# Level_Shifter.net
KiCad netlist of a schematic drawn in Altium Designer
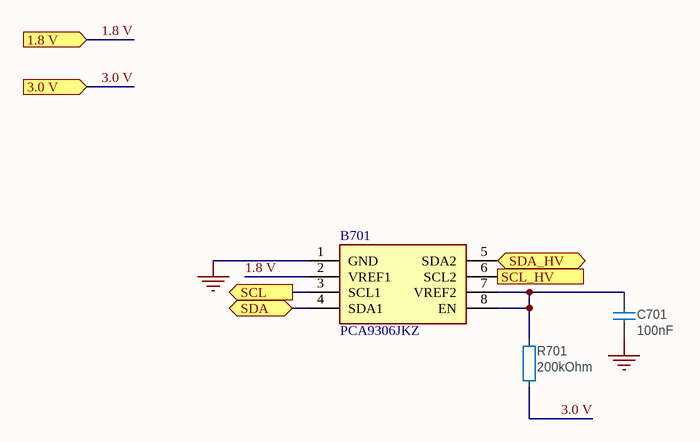
[diagram p0: Level Shifter (PCA9306JKZ).SchDoc]

(export (version "E")
  (design (tool "Eeschema 10.0.6"))
  (components
    (comp (ref "B701")
      (value "PCA9306JKZ")
      (footprint "PCA9306JKZ")
      (description "Dual Supply bidirectional I2C-bus and SMBus voltage-level translator")
      (fields (field (name "MANUFACTURER") "NXP Semiconductors"))
      (libsource (lib "Watch_Components") (part "PCA9306JKZ"))
    )
    (comp (ref "C701")
      (value "100nF")
      (footprint "CAPC0603X03L_C")
      (description "Capacitor, X7S, ±10%")
      (fields (field (name "AUTHOR") "rsk"))
      (libsource (lib "Watch_Components") (part "C0201-100n-16V-X7S"))
    )
    (comp (ref "R701")
      (value "200kOhm")
      (footprint "RESC0603X03L_C")
      (description "Resistor, ±1%, 0.05W")
      (fields (field (name "AUTHOR") "rsk"))
      (libsource (lib "Watch_Components") (part "R0201-2R2"))
    )
  )
  (nets
    (net (code "1") (name "/1.8 V") (class "Default")
      (node (ref "B701") (pin "2") (pinfunction "VREF1_2") (pintype "passive"))
    )
    (net (code "2") (name "/3.0 V") (class "Default")
      (node (ref "R701") (pin "1") (pinfunction "1_1") (pintype "passive"))
    )
    (net (code "3") (name "/SCL") (class "Default")
      (node (ref "B701") (pin "3") (pinfunction "SCL1_3") (pintype "passive"))
    )
    (net (code "4") (name "/SCL_HV") (class "Default")
      (node (ref "B701") (pin "6") (pinfunction "SCL2_6") (pintype "passive"))
    )
    (net (code "5") (name "/SDA") (class "Default")
      (node (ref "B701") (pin "4") (pinfunction "SDA1_4") (pintype "passive"))
    )
    (net (code "6") (name "/SDA_HV") (class "Default")
      (node (ref "B701") (pin "5") (pinfunction "SDA2_5") (pintype "passive"))
    )
    (net (code "7") (name "GND") (class "Default")
      (node (ref "B701") (pin "1") (pinfunction "GND_1") (pintype "passive"))
      (node (ref "C701") (pin "1") (pinfunction "1_1") (pintype "passive"))
    )
    (net (code "8") (name "Net-(B701-EN)") (class "Default")
      (node (ref "B701") (pin "7") (pinfunction "VREF2_7") (pintype "passive"))
      (node (ref "B701") (pin "8") (pinfunction "EN_8") (pintype "passive"))
      (node (ref "C701") (pin "2") (pinfunction "2_2") (pintype "passive"))
      (node (ref "R701") (pin "2") (pinfunction "2_2") (pintype "passive"))
    )
  )
)
